# 03_MCU.net
KiCad netlist of a schematic drawn in Altium Designer
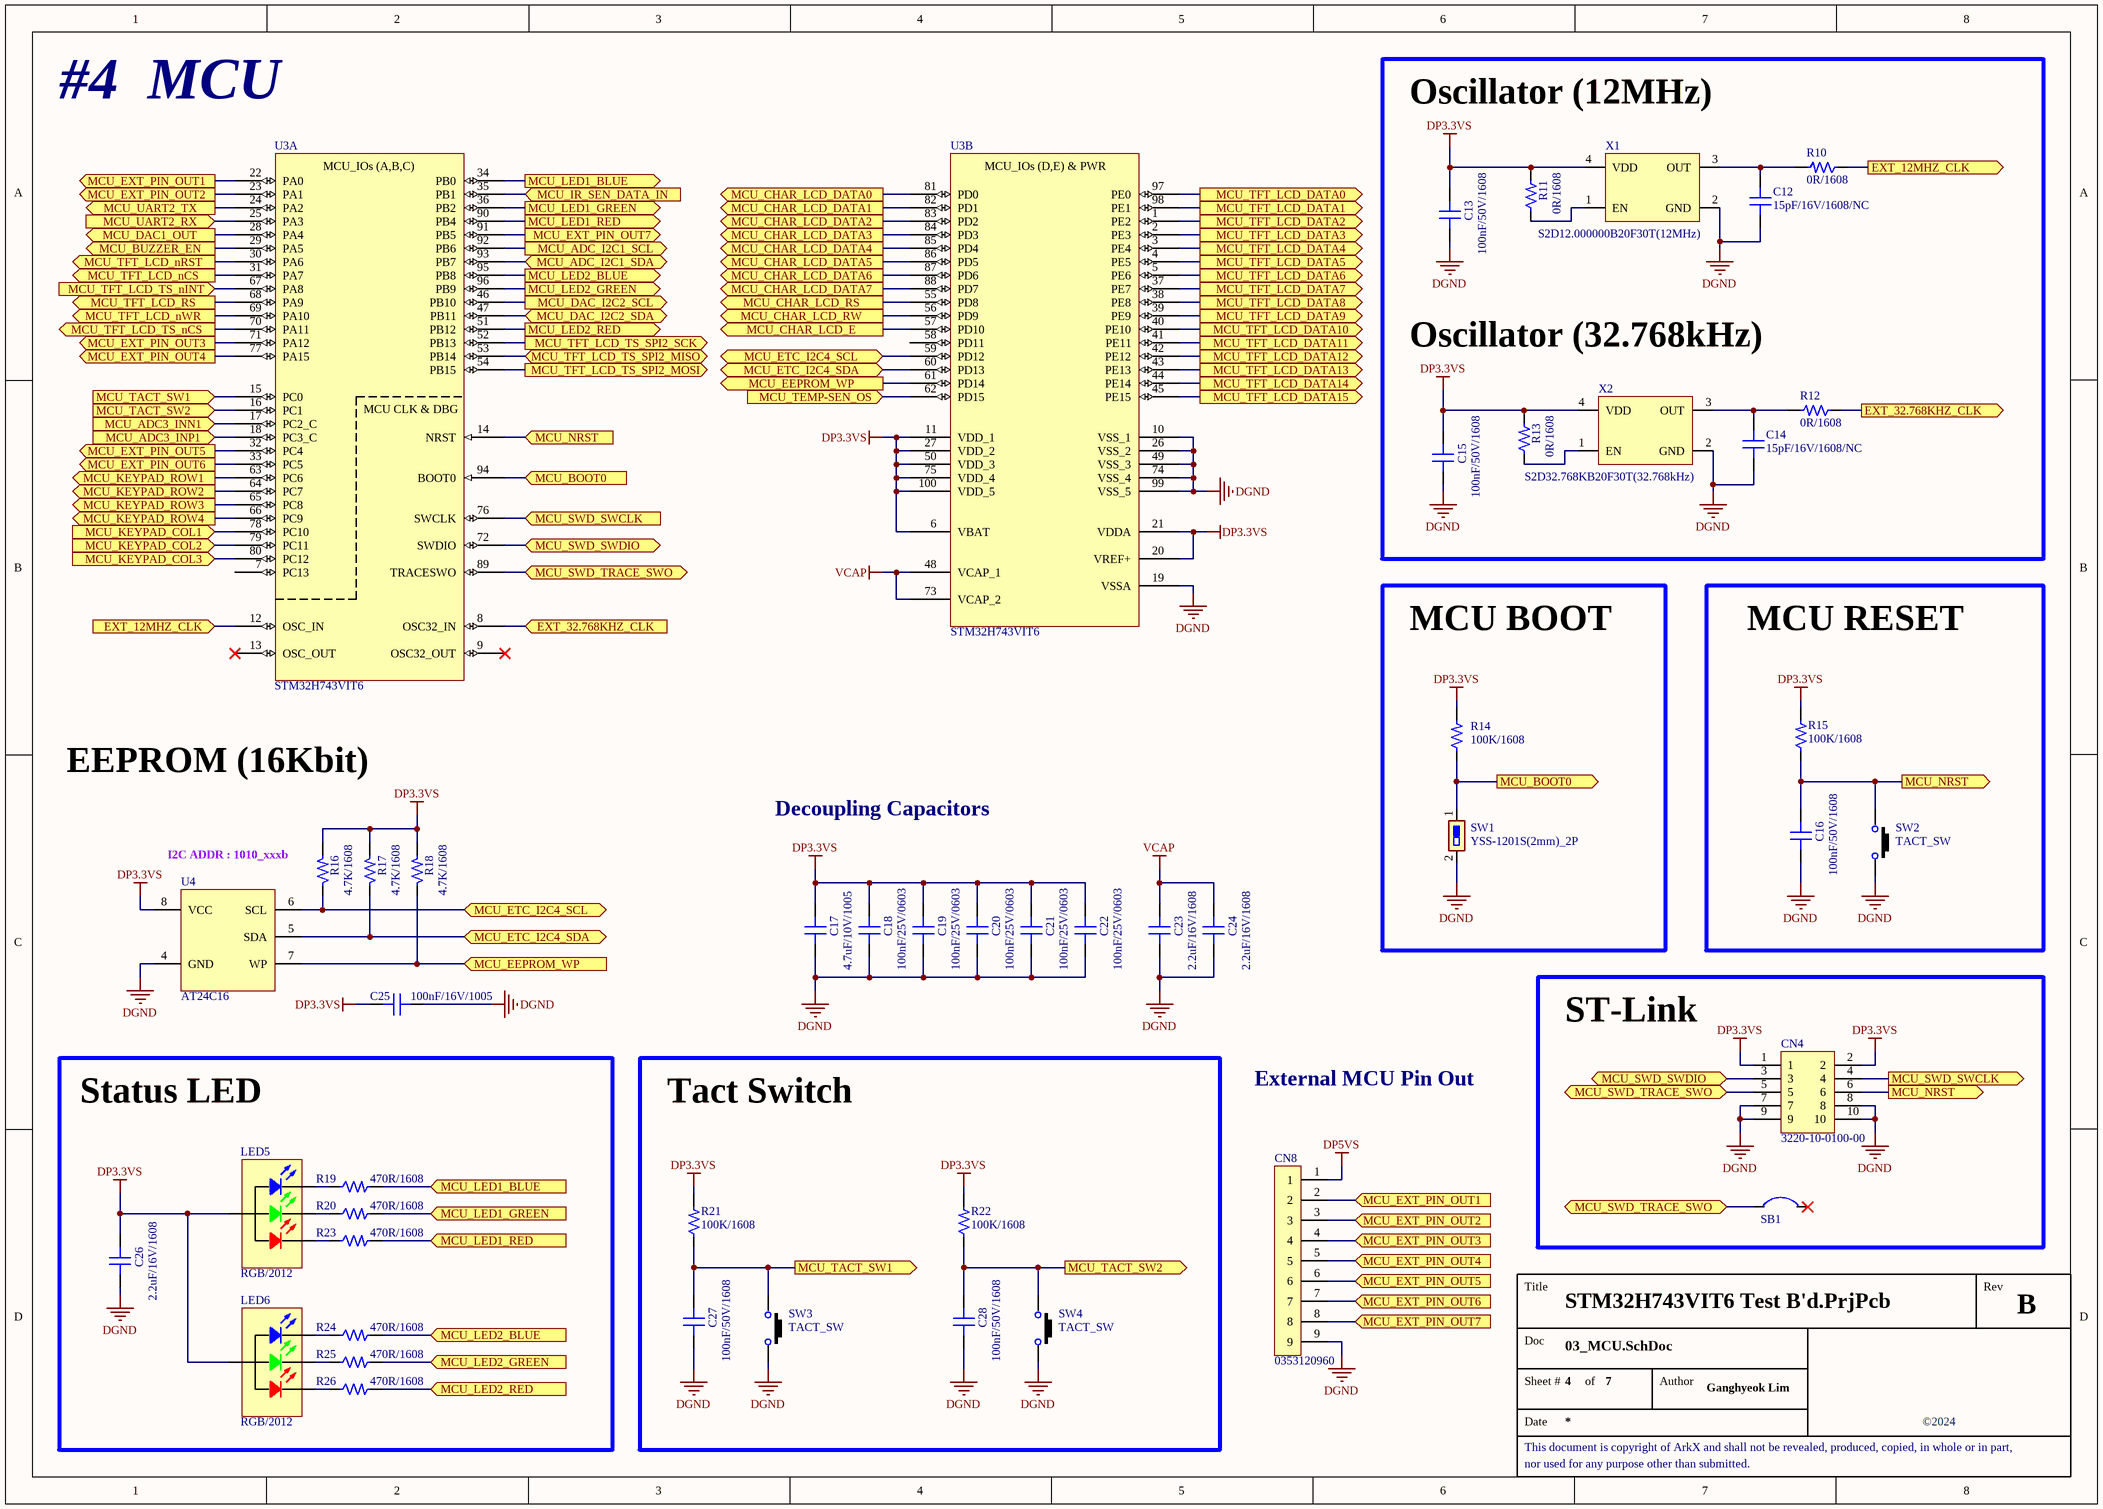
[diagram p0: 03_MCU.SchDoc]

(export (version "E")
  (design (tool "Eeschema 10.0.6"))
  (components
    (comp (ref "C12")
      (value "15pF/16V/1608/NC")
      (footprint "CAP 1608 (0603_INCH)/NC")
      (description "Ceramic CAP_15pF/16V/1608")
      (libsource (lib "Arkx") (part "CAP_NC_15pF/16V/1608"))
    )
    (comp (ref "C13")
      (value "100nF/50V/1608")
      (footprint "CAP 1608 (0603_INCH)")
      (description "Ceramic CAP_100nF/50V/1608")
      (fields (field (name "LCSC PART #") "C14663"))
      (libsource (lib "Arkx") (part "CAP_100nF/50V/1608"))
    )
    (comp (ref "C14")
      (value "15pF/16V/1608/NC")
      (footprint "CAP 1608 (0603_INCH)/NC")
      (description "Ceramic CAP_15pF/16V/1608")
      (libsource (lib "Arkx") (part "CAP_NC_15pF/16V/1608"))
    )
    (comp (ref "C15")
      (value "100nF/50V/1608")
      (footprint "CAP 1608 (0603_INCH)")
      (description "Ceramic CAP_100nF/50V/1608")
      (fields (field (name "LCSC PART #") "C14663"))
      (libsource (lib "Arkx") (part "CAP_100nF/50V/1608"))
    )
    (comp (ref "C16")
      (value "100nF/50V/1608")
      (footprint "CAP 1608 (0603_INCH)")
      (description "Ceramic CAP_100nF/50V/1608")
      (fields (field (name "LCSC PART #") "C14663"))
      (libsource (lib "Arkx") (part "CAP_100nF/50V/1608"))
    )
    (comp (ref "C17")
      (value "4.7uF/10V/1005")
      (footprint "CAP 1005 (0402_INCH)")
      (description "Ceramic CAP_4.7uF/10V/1005")
      (fields (field (name "LCSC PART #") "C23733"))
      (libsource (lib "Arkx") (part "CAP_4.7uF/10V/1005"))
    )
    (comp (ref "C18")
      (value "100nF/25V/0603")
      (footprint "CAP 0603 (0201_INCH)")
      (description "Ceramic CAP_100nF/25V/0603")
      (fields (field (name "LCSC PART #") "C181047"))
      (libsource (lib "Arkx") (part "CAP_100nF/25V/0603"))
    )
    (comp (ref "C19")
      (value "100nF/25V/0603")
      (footprint "CAP 0603 (0201_INCH)")
      (description "Ceramic CAP_100nF/25V/0603")
      (fields (field (name "LCSC PART #") "C181047"))
      (libsource (lib "Arkx") (part "CAP_100nF/25V/0603"))
    )
    (comp (ref "C20")
      (value "100nF/25V/0603")
      (footprint "CAP 0603 (0201_INCH)")
      (description "Ceramic CAP_100nF/25V/0603")
      (fields (field (name "LCSC PART #") "C181047"))
      (libsource (lib "Arkx") (part "CAP_100nF/25V/0603"))
    )
    (comp (ref "C21")
      (value "100nF/25V/0603")
      (footprint "CAP 0603 (0201_INCH)")
      (description "Ceramic CAP_100nF/25V/0603")
      (fields (field (name "LCSC PART #") "C181047"))
      (libsource (lib "Arkx") (part "CAP_100nF/25V/0603"))
    )
    (comp (ref "C22")
      (value "100nF/25V/0603")
      (footprint "CAP 0603 (0201_INCH)")
      (description "Ceramic CAP_100nF/25V/0603")
      (fields (field (name "LCSC PART #") "C181047"))
      (libsource (lib "Arkx") (part "CAP_100nF/25V/0603"))
    )
    (comp (ref "C23")
      (value "2.2uF/16V/1608")
      (footprint "CAP 1608 (0603_INCH)")
      (description "Ceramic CAP_2.2uF/16V/1608")
      (fields (field (name "LCSC PART #") "C23630"))
      (libsource (lib "Arkx") (part "CAP_2.2uF/16V/1608"))
    )
    (comp (ref "C24")
      (value "2.2uF/16V/1608")
      (footprint "CAP 1608 (0603_INCH)")
      (description "Ceramic CAP_2.2uF/16V/1608")
      (fields (field (name "LCSC PART #") "C23630"))
      (libsource (lib "Arkx") (part "CAP_2.2uF/16V/1608"))
    )
    (comp (ref "C25")
      (value "100nF/16V/1005")
      (footprint "CAP 1005 (0402_INCH)")
      (description "Ceramic CAP_100nF/16V/1005")
      (fields (field (name "LCSC PART #") "C1525"))
      (libsource (lib "Arkx") (part "CAP_100nF/16V/1005"))
    )
    (comp (ref "C26")
      (value "2.2uF/16V/1608")
      (footprint "CAP 1608 (0603_INCH)")
      (description "Ceramic CAP_2.2uF/16V/1608")
      (fields (field (name "LCSC PART #") "C23630"))
      (libsource (lib "Arkx") (part "CAP_2.2uF/16V/1608"))
    )
    (comp (ref "C27")
      (value "100nF/50V/1608")
      (footprint "CAP 1608 (0603_INCH)")
      (description "Ceramic CAP_100nF/50V/1608")
      (fields (field (name "LCSC PART #") "C14663"))
      (libsource (lib "Arkx") (part "CAP_100nF/50V/1608"))
    )
    (comp (ref "C28")
      (value "100nF/50V/1608")
      (footprint "CAP 1608 (0603_INCH)")
      (description "Ceramic CAP_100nF/50V/1608")
      (fields (field (name "LCSC PART #") "C14663"))
      (libsource (lib "Arkx") (part "CAP_100nF/50V/1608"))
    )
    (comp (ref "CN4")
      (value "3220-10-0100-00")
      (footprint "CON 3220-10-0100-00 (Hand_Solder)")
      (description "CONN HEADER VERT 10POS 1.27MM")
      (libsource (lib "Arkx") (part "CON_IDC_3220-10-0100-00"))
    )
    (comp (ref "CN8")
      (value "0353120960")
      (footprint "CON 0353120960 (MOLEX)")
      (description "CONN HEADER VERT 9POS 2.5MM")
      (libsource (lib "Arkx") (part "CON_0353120960"))
    )
    (comp (ref "LED5")
      (value "RGB/2012")
      (footprint "LED MHT170RGBCT")
      (fields (field (name "LCSC PART #") "C2962094"))
      (libsource (lib "Arkx") (part "LED_RGB_MHT170RGBCT"))
    )
    (comp (ref "LED6")
      (value "RGB/2012")
      (footprint "LED MHT170RGBCT")
      (fields (field (name "LCSC PART #") "C2962094"))
      (libsource (lib "Arkx") (part "LED_RGB_MHT170RGBCT"))
    )
    (comp (ref "R10")
      (value "0R/1608")
      (footprint "RES 1608 (0603_inch)")
      (description "RES_0R/1608/0.1W")
      (fields (field (name "LCSC PART #") "C21189"))
      (libsource (lib "Arkx") (part "RES_0R/1608/0.1W"))
    )
    (comp (ref "R11")
      (value "0R/1608")
      (footprint "RES 1608 (0603_inch)")
      (description "RES_0R/1608/0.1W")
      (fields (field (name "LCSC PART #") "C21189"))
      (libsource (lib "Arkx") (part "RES_0R/1608/0.1W"))
    )
    (comp (ref "R12")
      (value "0R/1608")
      (footprint "RES 1608 (0603_inch)")
      (description "RES_0R/1608/0.1W")
      (fields (field (name "LCSC PART #") "C21189"))
      (libsource (lib "Arkx") (part "RES_0R/1608/0.1W"))
    )
    (comp (ref "R13")
      (value "0R/1608")
      (footprint "RES 1608 (0603_inch)")
      (description "RES_0R/1608/0.1W")
      (fields (field (name "LCSC PART #") "C21189"))
      (libsource (lib "Arkx") (part "RES_0R/1608/0.1W"))
    )
    (comp (ref "R14")
      (value "100K/1608")
      (footprint "RES 1608 (0603_inch)")
      (description "RES_100K/1608/0.1W")
      (fields (field (name "LCSC PART #") "C25803"))
      (libsource (lib "Arkx") (part "RES_100K/1608/0.1W"))
    )
    (comp (ref "R15")
      (value "100K/1608")
      (footprint "RES 1608 (0603_inch)")
      (description "RES_100K/1608/0.1W")
      (fields (field (name "LCSC PART #") "C25803"))
      (libsource (lib "Arkx") (part "RES_100K/1608/0.1W"))
    )
    (comp (ref "R16")
      (value "4.7K/1608")
      (footprint "RES 1608 (0603_inch)")
      (description "RES_4.7K/1608/0.1W")
      (fields (field (name "LCSC PART #") "C23162"))
      (libsource (lib "Arkx") (part "RES_4.7K/1608/0.1W"))
    )
    (comp (ref "R17")
      (value "4.7K/1608")
      (footprint "RES 1608 (0603_inch)")
      (description "RES_4.7K/1608/0.1W")
      (fields (field (name "LCSC PART #") "C23162"))
      (libsource (lib "Arkx") (part "RES_4.7K/1608/0.1W"))
    )
    (comp (ref "R18")
      (value "4.7K/1608")
      (footprint "RES 1608 (0603_inch)")
      (description "RES_4.7K/1608/0.1W")
      (fields (field (name "LCSC PART #") "C23162"))
      (libsource (lib "Arkx") (part "RES_4.7K/1608/0.1W"))
    )
    (comp (ref "R19")
      (value "470R/1608")
      (footprint "RES 1608 (0603_inch)")
      (description "RES_470R/1608/0.1W")
      (fields (field (name "LCSC PART #") "C23179"))
      (libsource (lib "Arkx") (part "RES_470R/1608/0.1W"))
    )
    (comp (ref "R20")
      (value "470R/1608")
      (footprint "RES 1608 (0603_inch)")
      (description "RES_470R/1608/0.1W")
      (fields (field (name "LCSC PART #") "C23179"))
      (libsource (lib "Arkx") (part "RES_470R/1608/0.1W"))
    )
    (comp (ref "R21")
      (value "100K/1608")
      (footprint "RES 1608 (0603_inch)")
      (description "RES_100K/1608/0.1W")
      (fields (field (name "LCSC PART #") "C25803"))
      (libsource (lib "Arkx") (part "RES_100K/1608/0.1W"))
    )
    (comp (ref "R22")
      (value "100K/1608")
      (footprint "RES 1608 (0603_inch)")
      (description "RES_100K/1608/0.1W")
      (fields (field (name "LCSC PART #") "C25803"))
      (libsource (lib "Arkx") (part "RES_100K/1608/0.1W"))
    )
    (comp (ref "R23")
      (value "470R/1608")
      (footprint "RES 1608 (0603_inch)")
      (description "RES_470R/1608/0.1W")
      (fields (field (name "LCSC PART #") "C23179"))
      (libsource (lib "Arkx") (part "RES_470R/1608/0.1W"))
    )
    (comp (ref "R24")
      (value "470R/1608")
      (footprint "RES 1608 (0603_inch)")
      (description "RES_470R/1608/0.1W")
      (fields (field (name "LCSC PART #") "C23179"))
      (libsource (lib "Arkx") (part "RES_470R/1608/0.1W"))
    )
    (comp (ref "R25")
      (value "470R/1608")
      (footprint "RES 1608 (0603_inch)")
      (description "RES_470R/1608/0.1W")
      (fields (field (name "LCSC PART #") "C23179"))
      (libsource (lib "Arkx") (part "RES_470R/1608/0.1W"))
    )
    (comp (ref "R26")
      (value "470R/1608")
      (footprint "RES 1608 (0603_inch)")
      (description "RES_470R/1608/0.1W")
      (fields (field (name "LCSC PART #") "C23179"))
      (libsource (lib "Arkx") (part "RES_470R/1608/0.1W"))
    )
    (comp (ref "SB1")
      (value "SB")
      (footprint "SB (Solder-Bridge)")
      (description "SB_Solder-Bridge")
      (libsource (lib "Arkx") (part "SB_Solder-Bridge"))
    )
    (comp (ref "SW1")
      (value "YSS-1201S(2mm)_2P")
      (footprint "SW YSS-1201S-2mm")
      (description "SMD Slide Switch.\r\nRating : DC 6V/0.3A\r\nTravel : 2MM")
      (libsource (lib "Arkx") (part "SW_YSS-1201S(2mm)_2P"))
    )
    (comp (ref "SW2")
      (value "TACT_SW")
      (footprint "SW K2-1102SP-C4SC-04")
      (fields (field (name "LCSC PART #") "C127509"))
      (libsource (lib "Arkx") (part "SW_K2-1102SP-C4SC-04(2P)"))
    )
    (comp (ref "SW3")
      (value "TACT_SW")
      (footprint "SW K2-1102SP-C4SC-04")
      (fields (field (name "LCSC PART #") "C127509"))
      (libsource (lib "Arkx") (part "SW_K2-1102SP-C4SC-04(2P)"))
    )
    (comp (ref "SW4")
      (value "TACT_SW")
      (footprint "SW K2-1102SP-C4SC-04")
      (fields (field (name "LCSC PART #") "C127509"))
      (libsource (lib "Arkx") (part "SW_K2-1102SP-C4SC-04(2P)"))
    )
    (comp (ref "U3")
      (value "STM32H743VIT6")
      (footprint "LQFP-100_14x14MM (ST)")
      (description "MCU High-performance & DSP DP-FPU, Arm Cortex-M7 MCU 2MBytes of Flash 1MB RAM, 480 M")
      (fields (field (name "LCSC PART #") "C114409"))
      (libsource (lib "Arkx") (part "IC_MCU_STM32H743VIT6"))
    )
    (comp (ref "U4")
      (value "AT24C16")
      (footprint "TSSOP-8_PW (TI)")
      (description "IC EEPROM 16KBIT I2C 1MHZ 8TSSOP")
      (fields (field (name "LCSC PART #") "C112954"))
      (libsource (lib "Arkx") (part "IC_EEPROM_AT24C16"))
    )
    (comp (ref "X1")
      (value "S2D12.000000B20F30T(12MHz)")
      (footprint "OSC SMD_2.5x2.0 (SCTF)")
      (description "3.3V~3.3V -40℃~+85℃ 20mA ±20ppm 12MHz SMD2520-4P  Oscillators ROHS")
      (fields (field (name "LCSC PART #") "C387449"))
      (libsource (lib "Arkx") (part "OSC_S2D12.000000B20F30T(12MHz)"))
    )
    (comp (ref "X2")
      (value "S2D32.768KB20F30T(32.768kHz)")
      (footprint "OSC SMD_2.5x2.0 (SCTF)")
      (description "3.3V ±20ppm CMOS 32.768kHz SMD2520-4P  Oscillators ROHS")
      (fields (field (name "LCSC PART #") "C387463"))
      (libsource (lib "Arkx") (part "OSC_S2D32.768KB20F30T(32.768kHz)"))
    )
  )
  (nets
    (net (code "1") (name "/EXT_12MHZ_CLK") (class "Default")
      (node (ref "R10") (pin "1") (pinfunction "1_1") (pintype "passive"))
      (node (ref "U3") (pin "12") (pinfunction "OSC_IN_12") (pintype "bidirectional"))
    )
    (net (code "2") (name "/EXT_32.768KHZ_CLK") (class "Default")
      (node (ref "R12") (pin "1") (pinfunction "1_1") (pintype "passive"))
      (node (ref "U3") (pin "8") (pinfunction "OSC32_IN_8") (pintype "bidirectional"))
    )
    (net (code "3") (name "/MCU_ADC3_INN1") (class "Default")
      (node (ref "U3") (pin "17") (pinfunction "PC2_C_17") (pintype "bidirectional"))
    )
    (net (code "4") (name "/MCU_ADC3_INP1") (class "Default")
      (node (ref "U3") (pin "18") (pinfunction "PC3_C_18") (pintype "bidirectional"))
    )
    (net (code "5") (name "/MCU_ADC_I2C1_SCL") (class "Default")
      (node (ref "U3") (pin "92") (pinfunction "PB6_92") (pintype "bidirectional"))
    )
    (net (code "6") (name "/MCU_ADC_I2C1_SDA") (class "Default")
      (node (ref "U3") (pin "93") (pinfunction "PB7_93") (pintype "bidirectional"))
    )
    (net (code "7") (name "/MCU_BOOT0") (class "Default")
      (node (ref "R14") (pin "1") (pinfunction "1_1") (pintype "passive"))
      (node (ref "SW1") (pin "1") (pinfunction "1_1") (pintype "passive"))
      (node (ref "U3") (pin "94") (pinfunction "BOOT0_94") (pintype "input"))
    )
    (net (code "8") (name "/MCU_BUZZER_EN") (class "Default")
      (node (ref "U3") (pin "29") (pinfunction "PA5_29") (pintype "bidirectional"))
    )
    (net (code "9") (name "/MCU_CHAR_LCD_DATA0") (class "Default")
      (node (ref "U3") (pin "81") (pinfunction "PD0_81") (pintype "bidirectional"))
    )
    (net (code "10") (name "/MCU_CHAR_LCD_DATA1") (class "Default")
      (node (ref "U3") (pin "82") (pinfunction "PD1_82") (pintype "bidirectional"))
    )
    (net (code "11") (name "/MCU_CHAR_LCD_DATA2") (class "Default")
      (node (ref "U3") (pin "83") (pinfunction "PD2_83") (pintype "bidirectional"))
    )
    (net (code "12") (name "/MCU_CHAR_LCD_DATA3") (class "Default")
      (node (ref "U3") (pin "84") (pinfunction "PD3_84") (pintype "bidirectional"))
    )
    (net (code "13") (name "/MCU_CHAR_LCD_DATA4") (class "Default")
      (node (ref "U3") (pin "85") (pinfunction "PD4_85") (pintype "bidirectional"))
    )
    (net (code "14") (name "/MCU_CHAR_LCD_DATA5") (class "Default")
      (node (ref "U3") (pin "86") (pinfunction "PD5_86") (pintype "bidirectional"))
    )
    (net (code "15") (name "/MCU_CHAR_LCD_DATA6") (class "Default")
      (node (ref "U3") (pin "87") (pinfunction "PD6_87") (pintype "bidirectional"))
    )
    (net (code "16") (name "/MCU_CHAR_LCD_DATA7") (class "Default")
      (node (ref "U3") (pin "88") (pinfunction "PD7_88") (pintype "bidirectional"))
    )
    (net (code "17") (name "/MCU_CHAR_LCD_E") (class "Default")
      (node (ref "U3") (pin "57") (pinfunction "PD10_57") (pintype "bidirectional"))
    )
    (net (code "18") (name "/MCU_CHAR_LCD_RS") (class "Default")
      (node (ref "U3") (pin "55") (pinfunction "PD8_55") (pintype "bidirectional"))
    )
    (net (code "19") (name "/MCU_CHAR_LCD_RW") (class "Default")
      (node (ref "U3") (pin "56") (pinfunction "PD9_56") (pintype "bidirectional"))
    )
    (net (code "20") (name "/MCU_DAC1_OUT") (class "Default")
      (node (ref "U3") (pin "28") (pinfunction "PA4_28") (pintype "bidirectional"))
    )
    (net (code "21") (name "/MCU_DAC_I2C2_SCL") (class "Default")
      (node (ref "U3") (pin "46") (pinfunction "PB10_46") (pintype "bidirectional"))
    )
    (net (code "22") (name "/MCU_DAC_I2C2_SDA") (class "Default")
      (node (ref "U3") (pin "47") (pinfunction "PB11_47") (pintype "bidirectional"))
    )
    (net (code "23") (name "/MCU_EEPROM_WP") (class "Default")
      (node (ref "R18") (pin "1") (pinfunction "1_1") (pintype "passive"))
      (node (ref "U3") (pin "61") (pinfunction "PD14_61") (pintype "bidirectional"))
      (node (ref "U4") (pin "7") (pinfunction "WP_7") (pintype "passive"))
    )
    (net (code "24") (name "/MCU_ETC_I2C4_SCL") (class "Default")
      (node (ref "R16") (pin "1") (pinfunction "1_1") (pintype "passive"))
      (node (ref "U3") (pin "59") (pinfunction "PD12_59") (pintype "bidirectional"))
      (node (ref "U4") (pin "6") (pinfunction "SCL_6") (pintype "passive"))
    )
    (net (code "25") (name "/MCU_ETC_I2C4_SDA") (class "Default")
      (node (ref "R17") (pin "1") (pinfunction "1_1") (pintype "passive"))
      (node (ref "U3") (pin "60") (pinfunction "PD13_60") (pintype "bidirectional"))
      (node (ref "U4") (pin "5") (pinfunction "SDA_5") (pintype "passive"))
    )
    (net (code "26") (name "/MCU_EXT_PIN_OUT1") (class "Default")
      (node (ref "CN8") (pin "2") (pinfunction "2_2") (pintype "passive"))
      (node (ref "U3") (pin "22") (pinfunction "PA0_22") (pintype "bidirectional"))
    )
    (net (code "27") (name "/MCU_EXT_PIN_OUT2") (class "Default")
      (node (ref "CN8") (pin "3") (pinfunction "3_3") (pintype "passive"))
      (node (ref "U3") (pin "23") (pinfunction "PA1_23") (pintype "bidirectional"))
    )
    (net (code "28") (name "/MCU_EXT_PIN_OUT3") (class "Default")
      (node (ref "CN8") (pin "4") (pinfunction "4_4") (pintype "passive"))
      (node (ref "U3") (pin "71") (pinfunction "PA12_71") (pintype "bidirectional"))
    )
    (net (code "29") (name "/MCU_EXT_PIN_OUT4") (class "Default")
      (node (ref "CN8") (pin "5") (pinfunction "5_5") (pintype "passive"))
      (node (ref "U3") (pin "77") (pinfunction "PA15_77") (pintype "bidirectional"))
    )
    (net (code "30") (name "/MCU_EXT_PIN_OUT5") (class "Default")
      (node (ref "CN8") (pin "6") (pinfunction "6_6") (pintype "passive"))
      (node (ref "U3") (pin "32") (pinfunction "PC4_32") (pintype "bidirectional"))
    )
    (net (code "31") (name "/MCU_EXT_PIN_OUT6") (class "Default")
      (node (ref "CN8") (pin "7") (pinfunction "7_7") (pintype "passive"))
      (node (ref "U3") (pin "33") (pinfunction "PC5_33") (pintype "bidirectional"))
    )
    (net (code "32") (name "/MCU_EXT_PIN_OUT7") (class "Default")
      (node (ref "CN8") (pin "8") (pinfunction "8_8") (pintype "passive"))
      (node (ref "U3") (pin "91") (pinfunction "PB5_91") (pintype "bidirectional"))
    )
    (net (code "33") (name "/MCU_IR_SEN_DATA_IN") (class "Default")
      (node (ref "U3") (pin "35") (pinfunction "PB1_35") (pintype "bidirectional"))
    )
    (net (code "34") (name "/MCU_KEYPAD_COL1") (class "Default")
      (node (ref "U3") (pin "78") (pinfunction "PC10_78") (pintype "bidirectional"))
    )
    (net (code "35") (name "/MCU_KEYPAD_COL2") (class "Default")
      (node (ref "U3") (pin "79") (pinfunction "PC11_79") (pintype "bidirectional"))
    )
    (net (code "36") (name "/MCU_KEYPAD_COL3") (class "Default")
      (node (ref "U3") (pin "80") (pinfunction "PC12_80") (pintype "bidirectional"))
    )
    (net (code "37") (name "/MCU_KEYPAD_ROW1") (class "Default")
      (node (ref "U3") (pin "63") (pinfunction "PC6_63") (pintype "bidirectional"))
    )
    (net (code "38") (name "/MCU_KEYPAD_ROW2") (class "Default")
      (node (ref "U3") (pin "64") (pinfunction "PC7_64") (pintype "bidirectional"))
    )
    (net (code "39") (name "/MCU_KEYPAD_ROW3") (class "Default")
      (node (ref "U3") (pin "65") (pinfunction "PC8_65") (pintype "bidirectional"))
    )
    (net (code "40") (name "/MCU_KEYPAD_ROW4") (class "Default")
      (node (ref "U3") (pin "66") (pinfunction "PC9_66") (pintype "bidirectional"))
    )
    (net (code "41") (name "/MCU_LED1_BLUE") (class "Default")
      (node (ref "R19") (pin "2") (pinfunction "2_2") (pintype "passive"))
      (node (ref "U3") (pin "34") (pinfunction "PB0_34") (pintype "bidirectional"))
    )
    (net (code "42") (name "/MCU_LED1_GREEN") (class "Default")
      (node (ref "R20") (pin "2") (pinfunction "2_2") (pintype "passive"))
      (node (ref "U3") (pin "36") (pinfunction "PB2_36") (pintype "bidirectional"))
    )
    (net (code "43") (name "/MCU_LED1_RED") (class "Default")
      (node (ref "R23") (pin "2") (pinfunction "2_2") (pintype "passive"))
      (node (ref "U3") (pin "90") (pinfunction "PB4_90") (pintype "bidirectional"))
    )
    (net (code "44") (name "/MCU_LED2_BLUE") (class "Default")
      (node (ref "R24") (pin "2") (pinfunction "2_2") (pintype "passive"))
      (node (ref "U3") (pin "95") (pinfunction "PB8_95") (pintype "bidirectional"))
    )
    (net (code "45") (name "/MCU_LED2_GREEN") (class "Default")
      (node (ref "R25") (pin "2") (pinfunction "2_2") (pintype "passive"))
      (node (ref "U3") (pin "96") (pinfunction "PB9_96") (pintype "bidirectional"))
    )
    (net (code "46") (name "/MCU_LED2_RED") (class "Default")
      (node (ref "R26") (pin "2") (pinfunction "2_2") (pintype "passive"))
      (node (ref "U3") (pin "51") (pinfunction "PB12_51") (pintype "bidirectional"))
    )
    (net (code "47") (name "/MCU_NRST") (class "Default")
      (node (ref "C16") (pin "2") (pinfunction "2_2") (pintype "passive"))
      (node (ref "CN4") (pin "6") (pinfunction "6_6") (pintype "passive"))
      (node (ref "R15") (pin "1") (pinfunction "1_1") (pintype "passive"))
      (node (ref "SW2") (pin "3") (pinfunction "3_3") (pintype "passive"))
      (node (ref "U3") (pin "14") (pinfunction "NRST_14") (pintype "input"))
    )
    (net (code "48") (name "/MCU_SWD_SWCLK") (class "Default")
      (node (ref "CN4") (pin "4") (pinfunction "4_4") (pintype "passive"))
      (node (ref "U3") (pin "76") (pinfunction "SWCLK_76") (pintype "bidirectional"))
    )
    (net (code "49") (name "/MCU_SWD_SWDIO") (class "Default")
      (node (ref "CN4") (pin "3") (pinfunction "3_3") (pintype "passive"))
      (node (ref "U3") (pin "72") (pinfunction "SWDIO_72") (pintype "bidirectional"))
    )
    (net (code "50") (name "/MCU_SWD_TRACE_SWO") (class "Default")
      (node (ref "CN4") (pin "5") (pinfunction "5_5") (pintype "passive"))
      (node (ref "SB1") (pin "1") (pinfunction "1_1") (pintype "passive"))
      (node (ref "U3") (pin "89") (pinfunction "TRACESWO_89") (pintype "bidirectional"))
    )
    (net (code "51") (name "/MCU_TACT_SW1") (class "Default")
      (node (ref "C27") (pin "2") (pinfunction "2_2") (pintype "passive"))
      (node (ref "R21") (pin "1") (pinfunction "1_1") (pintype "passive"))
      (node (ref "SW3") (pin "3") (pinfunction "3_3") (pintype "passive"))
      (node (ref "U3") (pin "15") (pinfunction "PC0_15") (pintype "bidirectional"))
    )
    (net (code "52") (name "/MCU_TACT_SW2") (class "Default")
      (node (ref "C28") (pin "2") (pinfunction "2_2") (pintype "passive"))
      (node (ref "R22") (pin "1") (pinfunction "1_1") (pintype "passive"))
      (node (ref "SW4") (pin "3") (pinfunction "3_3") (pintype "passive"))
      (node (ref "U3") (pin "16") (pinfunction "PC1_16") (pintype "bidirectional"))
    )
    (net (code "53") (name "/MCU_TEMP-SEN_OS") (class "Default")
      (node (ref "U3") (pin "62") (pinfunction "PD15_62") (pintype "bidirectional"))
    )
    (net (code "54") (name "/MCU_TFT_LCD_DATA0") (class "Default")
      (node (ref "U3") (pin "97") (pinfunction "PE0_97") (pintype "bidirectional"))
    )
    (net (code "55") (name "/MCU_TFT_LCD_DATA1") (class "Default")
      (node (ref "U3") (pin "98") (pinfunction "PE1_98") (pintype "bidirectional"))
    )
    (net (code "56") (name "/MCU_TFT_LCD_DATA2") (class "Default")
      (node (ref "U3") (pin "1") (pinfunction "PE2_1") (pintype "bidirectional"))
    )
    (net (code "57") (name "/MCU_TFT_LCD_DATA3") (class "Default")
      (node (ref "U3") (pin "2") (pinfunction "PE3_2") (pintype "bidirectional"))
    )
    (net (code "58") (name "/MCU_TFT_LCD_DATA4") (class "Default")
      (node (ref "U3") (pin "3") (pinfunction "PE4_3") (pintype "bidirectional"))
    )
    (net (code "59") (name "/MCU_TFT_LCD_DATA5") (class "Default")
      (node (ref "U3") (pin "4") (pinfunction "PE5_4") (pintype "bidirectional"))
    )
    (net (code "60") (name "/MCU_TFT_LCD_DATA6") (class "Default")
      (node (ref "U3") (pin "5") (pinfunction "PE6_5") (pintype "bidirectional"))
    )
    (net (code "61") (name "/MCU_TFT_LCD_DATA7") (class "Default")
      (node (ref "U3") (pin "37") (pinfunction "PE7_37") (pintype "bidirectional"))
    )
    (net (code "62") (name "/MCU_TFT_LCD_DATA8") (class "Default")
      (node (ref "U3") (pin "38") (pinfunction "PE8_38") (pintype "bidirectional"))
    )
    (net (code "63") (name "/MCU_TFT_LCD_DATA9") (class "Default")
      (node (ref "U3") (pin "39") (pinfunction "PE9_39") (pintype "bidirectional"))
    )
    (net (code "64") (name "/MCU_TFT_LCD_DATA10") (class "Default")
      (node (ref "U3") (pin "40") (pinfunction "PE10_40") (pintype "bidirectional"))
    )
    (net (code "65") (name "/MCU_TFT_LCD_DATA11") (class "Default")
      (node (ref "U3") (pin "41") (pinfunction "PE11_41") (pintype "bidirectional"))
    )
    (net (code "66") (name "/MCU_TFT_LCD_DATA12") (class "Default")
      (node (ref "U3") (pin "42") (pinfunction "PE12_42") (pintype "bidirectional"))
    )
    (net (code "67") (name "/MCU_TFT_LCD_DATA13") (class "Default")
      (node (ref "U3") (pin "43") (pinfunction "PE13_43") (pintype "bidirectional"))
    )
    (net (code "68") (name "/MCU_TFT_LCD_DATA14") (class "Default")
      (node (ref "U3") (pin "44") (pinfunction "PE14_44") (pintype "bidirectional"))
    )
    (net (code "69") (name "/MCU_TFT_LCD_DATA15") (class "Default")
      (node (ref "U3") (pin "45") (pinfunction "PE15_45") (pintype "bidirectional"))
    )
    (net (code "70") (name "/MCU_TFT_LCD_RS") (class "Default")
      (node (ref "U3") (pin "68") (pinfunction "PA9_68") (pintype "bidirectional"))
    )
    (net (code "71") (name "/MCU_TFT_LCD_TS_SPI2_MISO") (class "Default")
      (node (ref "U3") (pin "53") (pinfunction "PB14_53") (pintype "bidirectional"))
    )
    (net (code "72") (name "/MCU_TFT_LCD_TS_SPI2_MOSI") (class "Default")
      (node (ref "U3") (pin "54") (pinfunction "PB15_54") (pintype "bidirectional"))
    )
    (net (code "73") (name "/MCU_TFT_LCD_TS_SPI2_SCK") (class "Default")
      (node (ref "U3") (pin "52") (pinfunction "PB13_52") (pintype "bidirectional"))
    )
    (net (code "74") (name "/MCU_TFT_LCD_TS_nCS") (class "Default")
      (node (ref "U3") (pin "70") (pinfunction "PA11_70") (pintype "bidirectional"))
    )
    (net (code "75") (name "/MCU_TFT_LCD_TS_nINT") (class "Default")
      (node (ref "U3") (pin "67") (pinfunction "PA8_67") (pintype "bidirectional"))
    )
    (net (code "76") (name "/MCU_TFT_LCD_nCS") (class "Default")
      (node (ref "U3") (pin "31") (pinfunction "PA7_31") (pintype "bidirectional"))
    )
    (net (code "77") (name "/MCU_TFT_LCD_nRST") (class "Default")
      (node (ref "U3") (pin "30") (pinfunction "PA6_30") (pintype "bidirectional"))
    )
    (net (code "78") (name "/MCU_TFT_LCD_nWR") (class "Default")
      (node (ref "U3") (pin "69") (pinfunction "PA10_69") (pintype "bidirectional"))
    )
    (net (code "79") (name "/MCU_UART2_RX") (class "Default")
      (node (ref "U3") (pin "25") (pinfunction "PA3_25") (pintype "bidirectional"))
    )
    (net (code "80") (name "/MCU_UART2_TX") (class "Default")
      (node (ref "U3") (pin "24") (pinfunction "PA2_24") (pintype "bidirectional"))
    )
    (net (code "81") (name "DGND") (class "Default")
      (node (ref "C12") (pin "1") (pinfunction "1_1") (pintype "passive"))
      (node (ref "C13") (pin "1") (pinfunction "1_1") (pintype "passive"))
      (node (ref "C14") (pin "1") (pinfunction "1_1") (pintype "passive"))
      (node (ref "C15") (pin "1") (pinfunction "1_1") (pintype "passive"))
      (node (ref "C16") (pin "1") (pinfunction "1_1") (pintype "passive"))
      (node (ref "C17") (pin "1") (pinfunction "1_1") (pintype "passive"))
      (node (ref "C18") (pin "1") (pinfunction "1_1") (pintype "passive"))
      (node (ref "C19") (pin "1") (pinfunction "1_1") (pintype "passive"))
      (node (ref "C20") (pin "1") (pinfunction "1_1") (pintype "passive"))
      (node (ref "C21") (pin "1") (pinfunction "1_1") (pintype "passive"))
      (node (ref "C22") (pin "1") (pinfunction "1_1") (pintype "passive"))
      (node (ref "C23") (pin "2") (pinfunction "2_2") (pintype "passive"))
      (node (ref "C24") (pin "2") (pinfunction "2_2") (pintype "passive"))
      (node (ref "C25") (pin "1") (pinfunction "1_1") (pintype "passive"))
      (node (ref "C26") (pin "2") (pinfunction "2_2") (pintype "passive"))
      (node (ref "C27") (pin "1") (pinfunction "1_1") (pintype "passive"))
      (node (ref "C28") (pin "1") (pinfunction "1_1") (pintype "passive"))
      (node (ref "CN4") (pin "10") (pinfunction "10_10") (pintype "passive"))
      (node (ref "CN4") (pin "7") (pinfunction "7_7") (pintype "passive"))
      (node (ref "CN4") (pin "8") (pinfunction "8_8") (pintype "passive"))
      (node (ref "CN4") (pin "9") (pinfunction "9_9") (pintype "passive"))
      (node (ref "CN8") (pin "9") (pinfunction "9_9") (pintype "passive"))
      (node (ref "SW1") (pin "2") (pinfunction "2_2") (pintype "passive"))
      (node (ref "SW2") (pin "1") (pinfunction "1_1") (pintype "passive"))
      (node (ref "SW3") (pin "1") (pinfunction "1_1") (pintype "passive"))
      (node (ref "SW4") (pin "1") (pinfunction "1_1") (pintype "passive"))
      (node (ref "U3") (pin "10") (pinfunction "VSS_1_10") (pintype "power_in"))
      (node (ref "U3") (pin "19") (pinfunction "VSSA_19") (pintype "power_in"))
      (node (ref "U3") (pin "26") (pinfunction "VSS_2_26") (pintype "power_in"))
      (node (ref "U3") (pin "49") (pinfunction "VSS_3_49") (pintype "power_in"))
      (node (ref "U3") (pin "74") (pinfunction "VSS_4_74") (pintype "power_in"))
      (node (ref "U3") (pin "99") (pinfunction "VSS_5_99") (pintype "power_in"))
      (node (ref "U4") (pin "4") (pinfunction "GND_4") (pintype "passive"))
      (node (ref "X1") (pin "2") (pinfunction "GND_2") (pintype "passive"))
      (node (ref "X2") (pin "2") (pinfunction "GND_2") (pintype "passive"))
    )
    (net (code "82") (name "DP3.3VS") (class "Default")
      (node (ref "C13") (pin "2") (pinfunction "2_2") (pintype "passive"))
      (node (ref "C15") (pin "2") (pinfunction "2_2") (pintype "passive"))
      (node (ref "C17") (pin "2") (pinfunction "2_2") (pintype "passive"))
      (node (ref "C18") (pin "2") (pinfunction "2_2") (pintype "passive"))
      (node (ref "C19") (pin "2") (pinfunction "2_2") (pintype "passive"))
      (node (ref "C20") (pin "2") (pinfunction "2_2") (pintype "passive"))
      (node (ref "C21") (pin "2") (pinfunction "2_2") (pintype "passive"))
      (node (ref "C22") (pin "2") (pinfunction "2_2") (pintype "passive"))
      (node (ref "C25") (pin "2") (pinfunction "2_2") (pintype "passive"))
      (node (ref "C26") (pin "1") (pinfunction "1_1") (pintype "passive"))
      (node (ref "CN4") (pin "1") (pinfunction "1_1") (pintype "passive"))
      (node (ref "CN4") (pin "2") (pinfunction "2_2") (pintype "passive"))
      (node (ref "LED5") (pin "4") (pinfunction "Common_Anode_4") (pintype "passive"))
      (node (ref "LED6") (pin "4") (pinfunction "Common_Anode_4") (pintype "passive"))
      (node (ref "R11") (pin "2") (pinfunction "2_2") (pintype "passive"))
      (node (ref "R13") (pin "2") (pinfunction "2_2") (pintype "passive"))
      (node (ref "R14") (pin "2") (pinfunction "2_2") (pintype "passive"))
      (node (ref "R15") (pin "2") (pinfunction "2_2") (pintype "passive"))
      (node (ref "R16") (pin "2") (pinfunction "2_2") (pintype "passive"))
      (node (ref "R17") (pin "2") (pinfunction "2_2") (pintype "passive"))
      (node (ref "R18") (pin "2") (pinfunction "2_2") (pintype "passive"))
      (node (ref "R21") (pin "2") (pinfunction "2_2") (pintype "passive"))
      (node (ref "R22") (pin "2") (pinfunction "2_2") (pintype "passive"))
      (node (ref "U3") (pin "100") (pinfunction "VDD_5_100") (pintype "power_in"))
      (node (ref "U3") (pin "11") (pinfunction "VDD_1_11") (pintype "power_in"))
      (node (ref "U3") (pin "20") (pinfunction "VREF+_20") (pintype "power_in"))
      (node (ref "U3") (pin "21") (pinfunction "VDDA_21") (pintype "power_in"))
      (node (ref "U3") (pin "27") (pinfunction "VDD_2_27") (pintype "power_in"))
      (node (ref "U3") (pin "50") (pinfunction "VDD_3_50") (pintype "power_in"))
      (node (ref "U3") (pin "6") (pinfunction "VBAT_6") (pintype "power_in"))
      (node (ref "U3") (pin "75") (pinfunction "VDD_4_75") (pintype "power_in"))
      (node (ref "U4") (pin "8") (pinfunction "VCC_8") (pintype "passive"))
      (node (ref "X1") (pin "4") (pinfunction "VDD_4") (pintype "passive"))
      (node (ref "X2") (pin "4") (pinfunction "VDD_4") (pintype "passive"))
    )
    (net (code "83") (name "DP5VS") (class "Default")
      (node (ref "CN8") (pin "1") (pinfunction "1_1") (pintype "passive"))
    )
    (net (code "84") (name "Net-(LED5-BLUE)") (class "Default")
      (node (ref "LED5") (pin "3") (pinfunction "BLUE_3") (pintype "passive"))
      (node (ref "R19") (pin "1") (pinfunction "1_1") (pintype "passive"))
    )
    (net (code "85") (name "Net-(LED5-GREEN)") (class "Default")
      (node (ref "LED5") (pin "2") (pinfunction "GREEN_2") (pintype "passive"))
      (node (ref "R20") (pin "1") (pinfunction "1_1") (pintype "passive"))
    )
    (net (code "86") (name "Net-(LED5-RED)") (class "Default")
      (node (ref "LED5") (pin "1") (pinfunction "RED_1") (pintype "passive"))
      (node (ref "R23") (pin "1") (pinfunction "1_1") (pintype "passive"))
    )
    (net (code "87") (name "Net-(LED6-BLUE)") (class "Default")
      (node (ref "LED6") (pin "3") (pinfunction "BLUE_3") (pintype "passive"))
      (node (ref "R24") (pin "1") (pinfunction "1_1") (pintype "passive"))
    )
    (net (code "88") (name "Net-(LED6-GREEN)") (class "Default")
      (node (ref "LED6") (pin "2") (pinfunction "GREEN_2") (pintype "passive"))
      (node (ref "R25") (pin "1") (pinfunction "1_1") (pintype "passive"))
    )
    (net (code "89") (name "Net-(LED6-RED)") (class "Default")
      (node (ref "LED6") (pin "1") (pinfunction "RED_1") (pintype "passive"))
      (node (ref "R26") (pin "1") (pinfunction "1_1") (pintype "passive"))
    )
    (net (code "90") (name "Net-(X1-EN)") (class "Default")
      (node (ref "R11") (pin "1") (pinfunction "1_1") (pintype "passive"))
      (node (ref "X1") (pin "1") (pinfunction "EN_1") (pintype "passive"))
    )
    (net (code "91") (name "Net-(X1-OUT)") (class "Default")
      (node (ref "C12") (pin "2") (pinfunction "2_2") (pintype "passive"))
      (node (ref "R10") (pin "2") (pinfunction "2_2") (pintype "passive"))
      (node (ref "X1") (pin "3") (pinfunction "OUT_3") (pintype "passive"))
    )
    (net (code "92") (name "Net-(X2-EN)") (class "Default")
      (node (ref "R13") (pin "1") (pinfunction "1_1") (pintype "passive"))
      (node (ref "X2") (pin "1") (pinfunction "EN_1") (pintype "passive"))
    )
    (net (code "93") (name "Net-(X2-OUT)") (class "Default")
      (node (ref "C14") (pin "2") (pinfunction "2_2") (pintype "passive"))
      (node (ref "R12") (pin "2") (pinfunction "2_2") (pintype "passive"))
      (node (ref "X2") (pin "3") (pinfunction "OUT_3") (pintype "passive"))
    )
    (net (code "94") (name "VCAP") (class "Default")
      (node (ref "C23") (pin "1") (pinfunction "1_1") (pintype "passive"))
      (node (ref "C24") (pin "1") (pinfunction "1_1") (pintype "passive"))
      (node (ref "U3") (pin "48") (pinfunction "VCAP_1_48") (pintype "power_in"))
      (node (ref "U3") (pin "73") (pinfunction "VCAP_2_73") (pintype "power_in"))
    )
    (net (code "95") (name "unconnected-(SB1-Pad2)") (class "Default")
      (node (ref "SB1") (pin "2") (pinfunction "2_2") (pintype "passive+no_connect"))
    )
    (net (code "96") (name "unconnected-(U3A-OSC32_OUT-Pad9)") (class "Default")
      (node (ref "U3") (pin "9") (pinfunction "OSC32_OUT_9") (pintype "bidirectional+no_connect"))
    )
    (net (code "97") (name "unconnected-(U3A-OSC_OUT-Pad13)") (class "Default")
      (node (ref "U3") (pin "13") (pinfunction "OSC_OUT_13") (pintype "bidirectional+no_connect"))
    )
    (net (code "98") (name "unconnected-(U3A-PC13-Pad7)") (class "Default")
      (node (ref "U3") (pin "7") (pinfunction "PC13_7") (pintype "bidirectional"))
    )
    (net (code "99") (name "unconnected-(U3B-PD11-Pad58)") (class "Default")
      (node (ref "U3") (pin "58") (pinfunction "PD11_58") (pintype "bidirectional"))
    )
  )
)
